# SIM900.net
KiCad netlist of a schematic drawn in Altium Designer
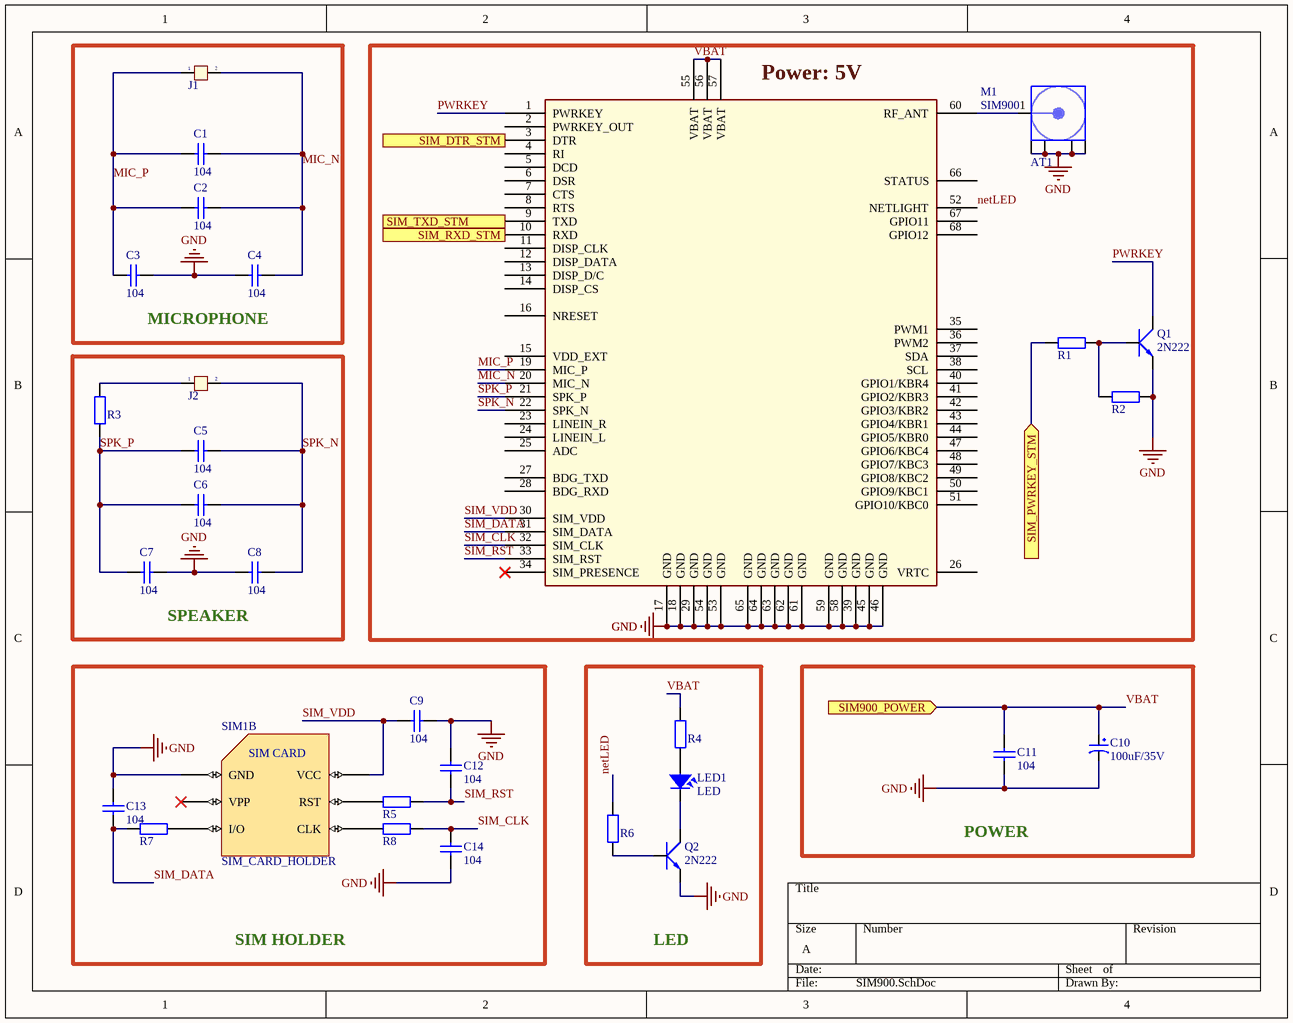
[diagram p0: SIM900.SchDoc]

(export (version "E")
  (design (tool "Eeschema 10.0.6"))
  (components
    (comp (ref "AT1")
      (value "AT-GSM-GPS")
      (footprint "SNW_H13-L17-SMA")
      (description "CONNECTER ANTENNA GPS GSM")
      (fields (field (name "MPN") "SNW_H13-L17-SMA") (field (name "MFR") "Sunny Way"))
      (libsource (lib "BYTECH_HW_LIB_2019 (1)") (part "SNW_H13-L17-SMA"))
    )
    (comp (ref "C1")
      (value "104")
      (footprint "0805")
      (description "Capacitor (Semiconductor SIM Model)")
      (fields (field (name "PUBLISHER") "Altium Limited"))
      (libsource (lib "Devzone_SCHLib") (part "Cap 104_SMD"))
    )
    (comp (ref "C2")
      (value "104")
      (footprint "0805")
      (description "Capacitor (Semiconductor SIM Model)")
      (fields (field (name "PUBLISHER") "Altium Limited"))
      (libsource (lib "Devzone_SCHLib") (part "Cap 104_SMD"))
    )
    (comp (ref "C3")
      (value "104")
      (footprint "0805")
      (description "Capacitor (Semiconductor SIM Model)")
      (fields (field (name "PUBLISHER") "Altium Limited"))
      (libsource (lib "Devzone_SCHLib") (part "Cap 104_SMD"))
    )
    (comp (ref "C4")
      (value "104")
      (footprint "0805")
      (description "Capacitor (Semiconductor SIM Model)")
      (fields (field (name "PUBLISHER") "Altium Limited"))
      (libsource (lib "Devzone_SCHLib") (part "Cap 104_SMD"))
    )
    (comp (ref "C5")
      (value "104")
      (footprint "0805")
      (description "Capacitor (Semiconductor SIM Model)")
      (fields (field (name "PUBLISHER") "Altium Limited"))
      (libsource (lib "Devzone_SCHLib") (part "Cap 104_SMD"))
    )
    (comp (ref "C6")
      (value "104")
      (footprint "0805")
      (description "Capacitor (Semiconductor SIM Model)")
      (fields (field (name "PUBLISHER") "Altium Limited"))
      (libsource (lib "Devzone_SCHLib") (part "Cap 104_SMD"))
    )
    (comp (ref "C7")
      (value "104")
      (footprint "0805")
      (description "Capacitor (Semiconductor SIM Model)")
      (fields (field (name "PUBLISHER") "Altium Limited"))
      (libsource (lib "Devzone_SCHLib") (part "Cap 104_SMD"))
    )
    (comp (ref "C8")
      (value "104")
      (footprint "0805")
      (description "Capacitor (Semiconductor SIM Model)")
      (fields (field (name "PUBLISHER") "Altium Limited"))
      (libsource (lib "Devzone_SCHLib") (part "Cap 104_SMD"))
    )
    (comp (ref "C9")
      (value "104")
      (footprint "0805")
      (description "Capacitor (Semiconductor SIM Model)")
      (fields (field (name "PUBLISHER") "Altium Limited"))
      (libsource (lib "Devzone_SCHLib") (part "Cap 104_SMD"))
    )
    (comp (ref "C10")
      (value "100uF/35V")
      (footprint "CP1.5/3.4")
      (description "Cap 100uF/35V - 470uF/16V")
      (libsource (lib "KhanhBK_Library_4") (part "CP3"))
    )
    (comp (ref "C11")
      (value "104")
      (footprint "0805")
      (description "Capacitor (Semiconductor SIM Model)")
      (fields (field (name "PUBLISHER") "Altium Limited"))
      (libsource (lib "Devzone_SCHLib") (part "Cap 104_SMD"))
    )
    (comp (ref "C12")
      (value "104")
      (footprint "0805")
      (description "Capacitor (Semiconductor SIM Model)")
      (fields (field (name "PUBLISHER") "Altium Limited"))
      (libsource (lib "Devzone_SCHLib") (part "Cap 104_SMD"))
    )
    (comp (ref "C13")
      (value "104")
      (footprint "0805")
      (description "Capacitor (Semiconductor SIM Model)")
      (fields (field (name "PUBLISHER") "Altium Limited"))
      (libsource (lib "Devzone_SCHLib") (part "Cap 104_SMD"))
    )
    (comp (ref "C14")
      (value "104")
      (footprint "0805")
      (description "Capacitor (Semiconductor SIM Model)")
      (fields (field (name "PUBLISHER") "Altium Limited"))
      (libsource (lib "Devzone_SCHLib") (part "Cap 104_SMD"))
    )
    (comp (ref "J1")
      (value "Jumper 2")
      (footprint "JP2")
      (libsource (lib "KhanhBK_SCH_Library_2") (part "JP 2"))
    )
    (comp (ref "J2")
      (value "Jumper 2")
      (footprint "JP2")
      (libsource (lib "KhanhBK_SCH_Library_2") (part "JP 2"))
    )
    (comp (ref "LED1")
      (value "LED")
      (footprint "SM-LED-1206-Green")
      (libsource (lib "KhanhBK_Library_4") (part "LED"))
    )
    (comp (ref "M1")
      (value "SIM900")
      (footprint "SIM900")
      (description "Quad-band GSM/GPRS module")
      (libsource (lib "KhanhBK_Library_4") (part "SIM900"))
    )
    (comp (ref "Q1")
      (value "2N222")
      (footprint "SOT23-231")
      (description "NPN 600mW, ECB")
      (libsource (lib "KhanhBK_Library_4") (part "2N222"))
    )
    (comp (ref "Q2")
      (value "2N222")
      (footprint "SOT23-231")
      (description "NPN 600mW, ECB")
      (libsource (lib "KhanhBK_Library_4") (part "2N222"))
    )
    (comp (ref "R1")
      (value "1k")
      (footprint "RES-SMD-0101")
      (description "Resistor R1/4W")
      (libsource (lib "KhanhBK_Library_4") (part "R"))
    )
    (comp (ref "R2")
      (value "1k")
      (footprint "RES-SMD-0101")
      (description "Resistor R1/4W")
      (libsource (lib "KhanhBK_Library_4") (part "R"))
    )
    (comp (ref "R3")
      (value "1k")
      (footprint "RES-SMD-0101")
      (description "Resistor R1/4W")
      (libsource (lib "KhanhBK_Library_4") (part "R"))
    )
    (comp (ref "R4")
      (value "1k")
      (footprint "RES-SMD-0101")
      (description "Resistor R1/4W")
      (libsource (lib "KhanhBK_Library_4") (part "R"))
    )
    (comp (ref "R5")
      (value "1k")
      (footprint "RES-SMD-0101")
      (description "Resistor R1/4W")
      (libsource (lib "KhanhBK_Library_4") (part "R"))
    )
    (comp (ref "R6")
      (value "1k")
      (footprint "RES-SMD-0101")
      (description "Resistor R1/4W")
      (libsource (lib "KhanhBK_Library_4") (part "R"))
    )
    (comp (ref "R7")
      (value "1k")
      (footprint "RES-SMD-0101")
      (description "Resistor R1/4W")
      (libsource (lib "KhanhBK_Library_4") (part "R"))
    )
    (comp (ref "R8")
      (value "1k")
      (footprint "RES-SMD-0101")
      (description "Resistor R1/4W")
      (libsource (lib "KhanhBK_Library_4") (part "R"))
    )
    (comp (ref "SIM1")
      (value "SIM_CARD_HOLDER")
      (footprint "SIM_HOLDER:SIM_HOLDER")
      (libsource (lib "SIM_HOLDER") (part "SIM_CARD_HOLDER"))
    )
  )
  (nets
    (net (code "1") (name "/MIC_N") (class "Default")
      (node (ref "C1") (pin "1") (pintype "passive"))
      (node (ref "C2") (pin "1") (pintype "passive"))
      (node (ref "C4") (pin "1") (pintype "passive"))
      (node (ref "J1") (pin "2") (pinfunction "2_2") (pintype "passive"))
      (node (ref "M1") (pin "20") (pinfunction "MIC_N_20") (pintype "passive"))
    )
    (net (code "2") (name "/MIC_P") (class "Default")
      (node (ref "C1") (pin "2") (pintype "passive"))
      (node (ref "C2") (pin "2") (pintype "passive"))
      (node (ref "C3") (pin "1") (pintype "passive"))
      (node (ref "J1") (pin "1") (pinfunction "1_1") (pintype "passive"))
      (node (ref "M1") (pin "19") (pinfunction "MIC_P_19") (pintype "passive"))
    )
    (net (code "3") (name "/PWRKEY") (class "Default")
      (node (ref "M1") (pin "1") (pinfunction "PWRKEY_1") (pintype "passive"))
      (node (ref "Q1") (pin "3") (pinfunction "C_3") (pintype "passive"))
    )
    (net (code "4") (name "/SIM_CLK") (class "Default")
      (node (ref "C14") (pin "1") (pintype "passive"))
      (node (ref "M1") (pin "32") (pinfunction "SIM_CLK_32") (pintype "passive"))
      (node (ref "R8") (pin "1") (pinfunction "1_1") (pintype "passive"))
    )
    (net (code "5") (name "/SIM_DATA") (class "Default")
      (node (ref "C13") (pin "1") (pintype "passive"))
      (node (ref "M1") (pin "31") (pinfunction "SIM_DATA_31") (pintype "passive"))
      (node (ref "R7") (pin "2") (pinfunction "2_2") (pintype "passive"))
    )
    (net (code "6") (name "/SIM_DTR_STM") (class "Default")
      (node (ref "M1") (pin "3") (pinfunction "DTR_3") (pintype "passive"))
    )
    (net (code "7") (name "/SIM_PWRKEY_STM") (class "Default")
      (node (ref "R1") (pin "1") (pinfunction "1_1") (pintype "passive"))
    )
    (net (code "8") (name "/SIM_RST") (class "Default")
      (node (ref "C12") (pin "2") (pintype "passive"))
      (node (ref "M1") (pin "33") (pinfunction "SIM_RST_33") (pintype "passive"))
      (node (ref "R5") (pin "1") (pinfunction "1_1") (pintype "passive"))
    )
    (net (code "9") (name "/SIM_RXD_STM") (class "Default")
      (node (ref "M1") (pin "10") (pinfunction "RXD_10") (pintype "passive"))
    )
    (net (code "10") (name "/SIM_TXD_STM") (class "Default")
      (node (ref "M1") (pin "9") (pinfunction "TXD_9") (pintype "passive"))
    )
    (net (code "11") (name "/SIM_VDD") (class "Default")
      (node (ref "C9") (pin "2") (pintype "passive"))
      (node (ref "M1") (pin "30") (pinfunction "SIM_VDD_30") (pintype "passive"))
      (node (ref "SIM1") (pin "227") (pinfunction "VCC_227") (pintype "bidirectional"))
    )
    (net (code "12") (name "/SPK_N") (class "Default")
      (node (ref "C5") (pin "2") (pintype "passive"))
      (node (ref "C6") (pin "2") (pintype "passive"))
      (node (ref "C8") (pin "2") (pintype "passive"))
      (node (ref "J2") (pin "2") (pinfunction "2_2") (pintype "passive"))
      (node (ref "M1") (pin "22") (pinfunction "SPK_N_22") (pintype "passive"))
    )
    (net (code "13") (name "/SPK_P") (class "Default")
      (node (ref "C5") (pin "1") (pintype "passive"))
      (node (ref "C6") (pin "1") (pintype "passive"))
      (node (ref "C7") (pin "1") (pintype "passive"))
      (node (ref "M1") (pin "21") (pinfunction "SPK_P_21") (pintype "passive"))
      (node (ref "R3") (pin "2") (pinfunction "2_2") (pintype "passive"))
    )
    (net (code "14") (name "/VBAT") (class "Default")
      (node (ref "C10") (pin "1") (pinfunction "1_1") (pintype "passive"))
      (node (ref "C11") (pin "2") (pintype "passive"))
      (node (ref "M1") (pin "55") (pinfunction "VBAT_55") (pintype "passive"))
      (node (ref "M1") (pin "56") (pinfunction "VBAT_56") (pintype "passive"))
      (node (ref "M1") (pin "57") (pinfunction "VBAT_57") (pintype "passive"))
      (node (ref "R4") (pin "1") (pinfunction "1_1") (pintype "passive"))
    )
    (net (code "15") (name "/netLED") (class "Default")
      (node (ref "M1") (pin "52") (pinfunction "NETLIGHT_52") (pintype "passive"))
      (node (ref "R6") (pin "2") (pinfunction "2_2") (pintype "passive"))
    )
    (net (code "16") (name "GND") (class "Default")
      (node (ref "AT1") (pin "2") (pinfunction "2_2") (pintype "power_in"))
      (node (ref "C10") (pin "2") (pinfunction "2_2") (pintype "passive"))
      (node (ref "C11") (pin "1") (pintype "passive"))
      (node (ref "C12") (pin "1") (pintype "passive"))
      (node (ref "C13") (pin "2") (pintype "passive"))
      (node (ref "C14") (pin "2") (pintype "passive"))
      (node (ref "C3") (pin "2") (pintype "passive"))
      (node (ref "C4") (pin "2") (pintype "passive"))
      (node (ref "C7") (pin "2") (pintype "passive"))
      (node (ref "C8") (pin "1") (pintype "passive"))
      (node (ref "C9") (pin "1") (pintype "passive"))
      (node (ref "M1") (pin "17") (pinfunction "GND_17") (pintype "passive"))
      (node (ref "M1") (pin "18") (pinfunction "GND_18") (pintype "passive"))
      (node (ref "M1") (pin "29") (pinfunction "GND_29") (pintype "passive"))
      (node (ref "M1") (pin "39") (pinfunction "GND_39") (pintype "passive"))
      (node (ref "M1") (pin "45") (pinfunction "GND_45") (pintype "passive"))
      (node (ref "M1") (pin "46") (pinfunction "GND_46") (pintype "passive"))
      (node (ref "M1") (pin "53") (pinfunction "GND_53") (pintype "passive"))
      (node (ref "M1") (pin "54") (pinfunction "GND_54") (pintype "passive"))
      (node (ref "M1") (pin "58") (pinfunction "GND_58") (pintype "passive"))
      (node (ref "M1") (pin "59") (pinfunction "GND_59") (pintype "passive"))
      (node (ref "M1") (pin "61") (pinfunction "GND_61") (pintype "passive"))
      (node (ref "M1") (pin "62") (pinfunction "GND_62") (pintype "passive"))
      (node (ref "M1") (pin "63") (pinfunction "GND_63") (pintype "passive"))
      (node (ref "M1") (pin "64") (pinfunction "GND_64") (pintype "passive"))
      (node (ref "M1") (pin "65") (pinfunction "GND_65") (pintype "passive"))
      (node (ref "Q1") (pin "1") (pinfunction "E_1") (pintype "passive"))
      (node (ref "Q2") (pin "1") (pinfunction "E_1") (pintype "passive"))
      (node (ref "R2") (pin "2") (pinfunction "2_2") (pintype "passive"))
      (node (ref "SIM1") (pin "224") (pinfunction "GND_224") (pintype "bidirectional"))
    )
    (net (code "17") (name "Net-(AT1-Signal)") (class "Default")
      (node (ref "AT1") (pin "1") (pinfunction "Signal_1") (pintype "passive"))
      (node (ref "M1") (pin "60") (pinfunction "RF_ANT_60") (pintype "passive"))
    )
    (net (code "18") (name "Net-(J2-Pad1)") (class "Default")
      (node (ref "J2") (pin "1") (pinfunction "1_1") (pintype "passive"))
      (node (ref "R3") (pin "1") (pinfunction "1_1") (pintype "passive"))
    )
    (net (code "19") (name "Net-(LED1-Pad1)") (class "Default")
      (node (ref "LED1") (pin "1") (pinfunction "1_1") (pintype "passive"))
      (node (ref "R4") (pin "2") (pinfunction "2_2") (pintype "passive"))
    )
    (net (code "20") (name "Net-(Q1-B)") (class "Default")
      (node (ref "Q1") (pin "2") (pinfunction "B_2") (pintype "passive"))
      (node (ref "R1") (pin "2") (pinfunction "2_2") (pintype "passive"))
      (node (ref "R2") (pin "1") (pinfunction "1_1") (pintype "passive"))
    )
    (net (code "21") (name "Net-(Q2-B)") (class "Default")
      (node (ref "Q2") (pin "2") (pinfunction "B_2") (pintype "passive"))
      (node (ref "R6") (pin "1") (pinfunction "1_1") (pintype "passive"))
    )
    (net (code "22") (name "Net-(Q2-C)") (class "Default")
      (node (ref "LED1") (pin "2") (pinfunction "2_2") (pintype "passive"))
      (node (ref "Q2") (pin "3") (pinfunction "C_3") (pintype "passive"))
    )
    (net (code "23") (name "Net-(SIM1B-CLK)") (class "Default")
      (node (ref "R8") (pin "2") (pinfunction "2_2") (pintype "passive"))
      (node (ref "SIM1") (pin "229") (pinfunction "CLK_229") (pintype "bidirectional"))
    )
    (net (code "24") (name "Net-(SIM1B-I{slash}O)") (class "Default")
      (node (ref "R7") (pin "1") (pinfunction "1_1") (pintype "passive"))
      (node (ref "SIM1") (pin "226") (pinfunction "I/O_226") (pintype "bidirectional"))
    )
    (net (code "25") (name "Net-(SIM1B-RST)") (class "Default")
      (node (ref "R5") (pin "2") (pinfunction "2_2") (pintype "passive"))
      (node (ref "SIM1") (pin "228") (pinfunction "RST_228") (pintype "bidirectional"))
    )
    (net (code "26") (name "unconnected-(AT1-Pad2)") (class "Default")
      (node (ref "AT1") (pin "2") (pinfunction "2_2") (pintype "passive"))
    )
    (net (code "27") (name "unconnected-(M1-ADC-Pad25)") (class "Default")
      (node (ref "M1") (pin "25") (pinfunction "ADC_25") (pintype "passive"))
    )
    (net (code "28") (name "unconnected-(M1-BDG_RXD-Pad28)") (class "Default")
      (node (ref "M1") (pin "28") (pinfunction "BDG_RXD_28") (pintype "passive"))
    )
    (net (code "29") (name "unconnected-(M1-BDG_TXD-Pad27)") (class "Default")
      (node (ref "M1") (pin "27") (pinfunction "BDG_TXD_27") (pintype "passive"))
    )
    (net (code "30") (name "unconnected-(M1-CTS-Pad7)") (class "Default")
      (node (ref "M1") (pin "7") (pinfunction "CTS_7") (pintype "passive"))
    )
    (net (code "31") (name "unconnected-(M1-DCD-Pad5)") (class "Default")
      (node (ref "M1") (pin "5") (pinfunction "DCD_5") (pintype "passive"))
    )
    (net (code "32") (name "unconnected-(M1-DISP_CLK-Pad11)") (class "Default")
      (node (ref "M1") (pin "11") (pinfunction "DISP_CLK_11") (pintype "passive"))
    )
    (net (code "33") (name "unconnected-(M1-DISP_CS-Pad14)") (class "Default")
      (node (ref "M1") (pin "14") (pinfunction "DISP_CS_14") (pintype "passive"))
    )
    (net (code "34") (name "unconnected-(M1-DISP_DATA-Pad12)") (class "Default")
      (node (ref "M1") (pin "12") (pinfunction "DISP_DATA_12") (pintype "passive"))
    )
    (net (code "35") (name "unconnected-(M1-DISP_D{slash}C-Pad13)") (class "Default")
      (node (ref "M1") (pin "13") (pinfunction "DISP_D/C_13") (pintype "passive"))
    )
    (net (code "36") (name "unconnected-(M1-DSR-Pad6)") (class "Default")
      (node (ref "M1") (pin "6") (pinfunction "DSR_6") (pintype "passive"))
    )
    (net (code "37") (name "unconnected-(M1-GPIO1{slash}KBR4-Pad40)") (class "Default")
      (node (ref "M1") (pin "40") (pinfunction "GPIO1/KBR4_40") (pintype "passive"))
    )
    (net (code "38") (name "unconnected-(M1-GPIO2{slash}KBR3-Pad41)") (class "Default")
      (node (ref "M1") (pin "41") (pinfunction "GPIO2/KBR3_41") (pintype "passive"))
    )
    (net (code "39") (name "unconnected-(M1-GPIO3{slash}KBR2-Pad42)") (class "Default")
      (node (ref "M1") (pin "42") (pinfunction "GPIO3/KBR2_42") (pintype "passive"))
    )
    (net (code "40") (name "unconnected-(M1-GPIO4{slash}KBR1-Pad43)") (class "Default")
      (node (ref "M1") (pin "43") (pinfunction "GPIO4/KBR1_43") (pintype "passive"))
    )
    (net (code "41") (name "unconnected-(M1-GPIO5{slash}KBR0-Pad44)") (class "Default")
      (node (ref "M1") (pin "44") (pinfunction "GPIO5/KBR0_44") (pintype "passive"))
    )
    (net (code "42") (name "unconnected-(M1-GPIO6{slash}KBC4-Pad47)") (class "Default")
      (node (ref "M1") (pin "47") (pinfunction "GPIO6/KBC4_47") (pintype "passive"))
    )
    (net (code "43") (name "unconnected-(M1-GPIO7{slash}KBC3-Pad48)") (class "Default")
      (node (ref "M1") (pin "48") (pinfunction "GPIO7/KBC3_48") (pintype "passive"))
    )
    (net (code "44") (name "unconnected-(M1-GPIO8{slash}KBC2-Pad49)") (class "Default")
      (node (ref "M1") (pin "49") (pinfunction "GPIO8/KBC2_49") (pintype "passive"))
    )
    (net (code "45") (name "unconnected-(M1-GPIO9{slash}KBC1-Pad50)") (class "Default")
      (node (ref "M1") (pin "50") (pinfunction "GPIO9/KBC1_50") (pintype "passive"))
    )
    (net (code "46") (name "unconnected-(M1-GPIO10{slash}KBC0-Pad51)") (class "Default")
      (node (ref "M1") (pin "51") (pinfunction "GPIO10/KBC0_51") (pintype "passive"))
    )
    (net (code "47") (name "unconnected-(M1-GPIO11-Pad67)") (class "Default")
      (node (ref "M1") (pin "67") (pinfunction "GPIO11_67") (pintype "passive"))
    )
    (net (code "48") (name "unconnected-(M1-GPIO12-Pad68)") (class "Default")
      (node (ref "M1") (pin "68") (pinfunction "GPIO12_68") (pintype "passive"))
    )
    (net (code "49") (name "unconnected-(M1-LINEIN_L-Pad24)") (class "Default")
      (node (ref "M1") (pin "24") (pinfunction "LINEIN_L_24") (pintype "passive"))
    )
    (net (code "50") (name "unconnected-(M1-LINEIN_R-Pad23)") (class "Default")
      (node (ref "M1") (pin "23") (pinfunction "LINEIN_R_23") (pintype "passive"))
    )
    (net (code "51") (name "unconnected-(M1-NRESET-Pad16)") (class "Default")
      (node (ref "M1") (pin "16") (pinfunction "NRESET_16") (pintype "passive"))
    )
    (net (code "52") (name "unconnected-(M1-PWM1-Pad35)") (class "Default")
      (node (ref "M1") (pin "35") (pinfunction "PWM1_35") (pintype "passive"))
    )
    (net (code "53") (name "unconnected-(M1-PWM2-Pad36)") (class "Default")
      (node (ref "M1") (pin "36") (pinfunction "PWM2_36") (pintype "passive"))
    )
    (net (code "54") (name "unconnected-(M1-PWRKEY_OUT-Pad2)") (class "Default")
      (node (ref "M1") (pin "2") (pinfunction "PWRKEY_OUT_2") (pintype "passive"))
    )
    (net (code "55") (name "unconnected-(M1-RI-Pad4)") (class "Default")
      (node (ref "M1") (pin "4") (pinfunction "RI_4") (pintype "passive"))
    )
    (net (code "56") (name "unconnected-(M1-RTS-Pad8)") (class "Default")
      (node (ref "M1") (pin "8") (pinfunction "RTS_8") (pintype "passive"))
    )
    (net (code "57") (name "unconnected-(M1-SCL-Pad38)") (class "Default")
      (node (ref "M1") (pin "38") (pinfunction "SCL_38") (pintype "passive"))
    )
    (net (code "58") (name "unconnected-(M1-SDA-Pad37)") (class "Default")
      (node (ref "M1") (pin "37") (pinfunction "SDA_37") (pintype "passive"))
    )
    (net (code "59") (name "unconnected-(M1-SIM_PRESENCE-Pad34)") (class "Default")
      (node (ref "M1") (pin "34") (pinfunction "SIM_PRESENCE_34") (pintype "passive+no_connect"))
    )
    (net (code "60") (name "unconnected-(M1-STATUS-Pad66)") (class "Default")
      (node (ref "M1") (pin "66") (pinfunction "STATUS_66") (pintype "passive"))
    )
    (net (code "61") (name "unconnected-(M1-VDD_EXT-Pad15)") (class "Default")
      (node (ref "M1") (pin "15") (pinfunction "VDD_EXT_15") (pintype "passive"))
    )
    (net (code "62") (name "unconnected-(M1-VRTC-Pad26)") (class "Default")
      (node (ref "M1") (pin "26") (pinfunction "VRTC_26") (pintype "passive"))
    )
    (net (code "63") (name "unconnected-(SIM1B-VPP-Pad225)") (class "Default")
      (node (ref "SIM1") (pin "225") (pinfunction "VPP_225") (pintype "bidirectional+no_connect"))
    )
  )
)
